# 4_USB.net
KiCad netlist of a schematic drawn in Altium Designer
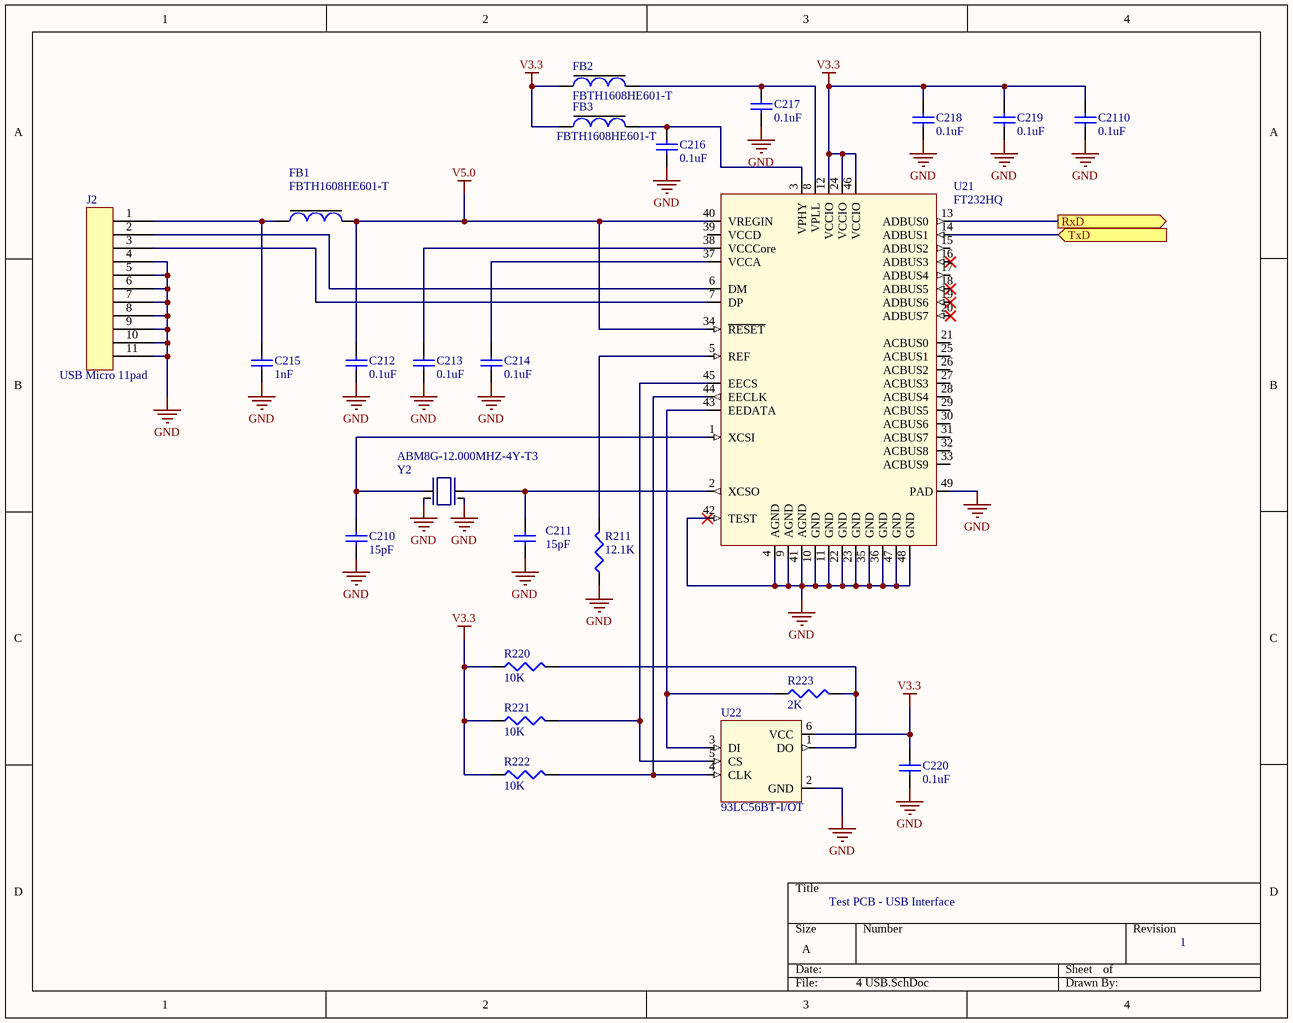
[diagram p0: 4 USB.SchDoc]

(export (version "E")
  (design (tool "Eeschema 10.0.6"))
  (components
    (comp (ref "C210")
      (value "15pF")
      (footprint "C0603")
      (description "Capacitor, SM")
      (fields (field (name "PUBLISHER") "Altium Limited"))
      (libsource (lib "Graylark") (part "Cap SM"))
    )
    (comp (ref "C211")
      (value "15pF")
      (footprint "C0603")
      (description "Capacitor, SM")
      (fields (field (name "PUBLISHER") "Altium Limited"))
      (libsource (lib "Graylark") (part "Cap SM"))
    )
    (comp (ref "C212")
      (value "0.1uF")
      (footprint "C0402")
      (description "Capacitor, SM")
      (fields (field (name "PUBLISHER") "Altium Limited"))
      (libsource (lib "Graylark") (part "Cap SM"))
    )
    (comp (ref "C213")
      (value "0.1uF")
      (footprint "C0402")
      (description "Capacitor, SM")
      (fields (field (name "PUBLISHER") "Altium Limited"))
      (libsource (lib "Graylark") (part "Cap SM"))
    )
    (comp (ref "C214")
      (value "0.1uF")
      (footprint "C0402")
      (description "Capacitor, SM")
      (fields (field (name "PUBLISHER") "Altium Limited"))
      (libsource (lib "Graylark") (part "Cap SM"))
    )
    (comp (ref "C215")
      (value "1nF")
      (footprint "C0603")
      (description "Capacitor, SM")
      (fields (field (name "PUBLISHER") "Altium Limited"))
      (libsource (lib "Graylark") (part "Cap SM"))
    )
    (comp (ref "C216")
      (value "0.1uF")
      (footprint "C0402")
      (description "Capacitor, SM")
      (fields (field (name "PUBLISHER") "Altium Limited"))
      (libsource (lib "Graylark") (part "Cap SM"))
    )
    (comp (ref "C217")
      (value "0.1uF")
      (footprint "C0402")
      (description "Capacitor, SM")
      (fields (field (name "PUBLISHER") "Altium Limited"))
      (libsource (lib "Graylark") (part "Cap SM"))
    )
    (comp (ref "C218")
      (value "0.1uF")
      (footprint "C0402")
      (description "Capacitor, SM")
      (fields (field (name "PUBLISHER") "Altium Limited"))
      (libsource (lib "Graylark") (part "Cap SM"))
    )
    (comp (ref "C219")
      (value "0.1uF")
      (footprint "C0402")
      (description "Capacitor, SM")
      (fields (field (name "PUBLISHER") "Altium Limited"))
      (libsource (lib "Graylark") (part "Cap SM"))
    )
    (comp (ref "C220")
      (value "0.1uF")
      (footprint "C0402")
      (description "Capacitor, SM")
      (fields (field (name "PUBLISHER") "Altium Limited"))
      (libsource (lib "Graylark") (part "Cap SM"))
    )
    (comp (ref "C2110")
      (value "0.1uF")
      (footprint "C0402")
      (description "Capacitor, SM")
      (fields (field (name "PUBLISHER") "Altium Limited"))
      (libsource (lib "Graylark") (part "Cap SM"))
    )
    (comp (ref "FB1")
      (value "FBTH1608HE601-T")
      (footprint "MPZ1608")
      (libsource (lib "Graylark") (part "Ferrite Bead"))
    )
    (comp (ref "FB2")
      (value "FBTH1608HE601-T")
      (footprint "MPZ1608")
      (libsource (lib "Graylark") (part "Ferrite Bead"))
    )
    (comp (ref "FB3")
      (value "FBTH1608HE601-T")
      (footprint "MPZ1608")
      (libsource (lib "Graylark") (part "Ferrite Bead"))
    )
    (comp (ref "J2")
      (value "USB Micro 11pad")
      (footprint "FCI 10118193")
      (libsource (lib "Graylark") (part "USB Micro 11pad"))
    )
    (comp (ref "R211")
      (value "12.1K")
      (footprint "R0603")
      (description "Resistor")
      (fields (field (name "PUBLISHER") "Altium Limited"))
      (libsource (lib "Graylark") (part "Res SM"))
    )
    (comp (ref "R220")
      (value "10K")
      (footprint "R0603")
      (description "Resistor")
      (fields (field (name "PUBLISHER") "Altium Limited"))
      (libsource (lib "Graylark") (part "Res SM"))
    )
    (comp (ref "R221")
      (value "10K")
      (footprint "R0603")
      (description "Resistor")
      (fields (field (name "PUBLISHER") "Altium Limited"))
      (libsource (lib "Graylark") (part "Res SM"))
    )
    (comp (ref "R222")
      (value "10K")
      (footprint "R0603")
      (description "Resistor")
      (fields (field (name "PUBLISHER") "Altium Limited"))
      (libsource (lib "Graylark") (part "Res SM"))
    )
    (comp (ref "R223")
      (value "2K")
      (footprint "R0603")
      (description "Resistor")
      (fields (field (name "PUBLISHER") "Altium Limited"))
      (libsource (lib "Graylark") (part "Res SM"))
    )
    (comp (ref "U21")
      (value "FT232HQ")
      (footprint "QFN50P800X800X100_HS-49N")
      (description "USB interface")
      (libsource (lib "Graylark_new") (part "FT232HQ"))
    )
    (comp (ref "U22")
      (value "93LC56BT-I/OT")
      (footprint "SOT23-6")
      (libsource (lib "Graylark") (part "93LC56BT-I/OT"))
    )
    (comp (ref "Y2")
      (value "ABM8G-12.000MHZ-4Y-T3")
      (footprint "7M Series XTAL")
      (libsource (lib "Graylark") (part "Crystal 4 Terminal"))
    )
  )
  (nets
    (net (code "1") (name "/RxD") (class "Default")
      (node (ref "U21") (pin "13") (pinfunction "ADBUS0_13") (pintype "output"))
    )
    (net (code "2") (name "/TxD") (class "Default")
      (node (ref "U21") (pin "14") (pinfunction "ADBUS1_14") (pintype "input"))
    )
    (net (code "3") (name "GND") (class "Default")
      (node (ref "C210") (pin "1") (pinfunction "1_1") (pintype "passive"))
      (node (ref "C211") (pin "1") (pinfunction "1_1") (pintype "passive"))
      (node (ref "C2110") (pin "1") (pinfunction "1_1") (pintype "passive"))
      (node (ref "C212") (pin "1") (pinfunction "1_1") (pintype "passive"))
      (node (ref "C213") (pin "1") (pinfunction "1_1") (pintype "passive"))
      (node (ref "C214") (pin "1") (pinfunction "1_1") (pintype "passive"))
      (node (ref "C215") (pin "1") (pinfunction "1_1") (pintype "passive"))
      (node (ref "C216") (pin "1") (pinfunction "1_1") (pintype "passive"))
      (node (ref "C217") (pin "1") (pinfunction "1_1") (pintype "passive"))
      (node (ref "C218") (pin "1") (pinfunction "1_1") (pintype "passive"))
      (node (ref "C219") (pin "1") (pinfunction "1_1") (pintype "passive"))
      (node (ref "C220") (pin "1") (pinfunction "1_1") (pintype "passive"))
      (node (ref "J2") (pin "10") (pinfunction "10_10") (pintype "power_in"))
      (node (ref "J2") (pin "11") (pinfunction "11_11") (pintype "power_in"))
      (node (ref "J2") (pin "4") (pinfunction "4_4") (pintype "passive"))
      (node (ref "J2") (pin "5") (pinfunction "5_5") (pintype "passive"))
      (node (ref "J2") (pin "6") (pinfunction "6_6") (pintype "passive"))
      (node (ref "J2") (pin "7") (pinfunction "7_7") (pintype "passive"))
      (node (ref "J2") (pin "8") (pinfunction "8_8") (pintype "passive"))
      (node (ref "J2") (pin "9") (pinfunction "9_9") (pintype "passive"))
      (node (ref "R211") (pin "1") (pinfunction "1_1") (pintype "passive"))
      (node (ref "U21") (pin "10") (pinfunction "GND_10") (pintype "power_in"))
      (node (ref "U21") (pin "11") (pinfunction "GND_11") (pintype "power_in"))
      (node (ref "U21") (pin "22") (pinfunction "GND_22") (pintype "power_in"))
      (node (ref "U21") (pin "23") (pinfunction "GND_23") (pintype "power_in"))
      (node (ref "U21") (pin "35") (pinfunction "GND_35") (pintype "power_in"))
      (node (ref "U21") (pin "36") (pinfunction "GND_36") (pintype "power_in"))
      (node (ref "U21") (pin "4") (pinfunction "AGND_4") (pintype "power_in"))
      (node (ref "U21") (pin "41") (pinfunction "AGND_41") (pintype "power_in"))
      (node (ref "U21") (pin "42") (pinfunction "TEST_42") (pintype "input"))
      (node (ref "U21") (pin "47") (pinfunction "GND_47") (pintype "power_in"))
      (node (ref "U21") (pin "48") (pinfunction "GND_48") (pintype "power_in"))
      (node (ref "U21") (pin "49") (pinfunction "PAD_49") (pintype "passive"))
      (node (ref "U21") (pin "9") (pinfunction "AGND_9") (pintype "power_in"))
      (node (ref "U22") (pin "2") (pinfunction "GND_2") (pintype "power_in"))
      (node (ref "Y2") (pin "2") (pinfunction "2_2") (pintype "passive"))
      (node (ref "Y2") (pin "4") (pinfunction "4_4") (pintype "passive"))
    )
    (net (code "4") (name "Net-(C215-Pad2)") (class "Default")
      (node (ref "C215") (pin "2") (pinfunction "2_2") (pintype "passive"))
      (node (ref "FB1") (pin "1") (pinfunction "1_1") (pintype "passive"))
      (node (ref "J2") (pin "1") (pinfunction "1_1") (pintype "passive"))
    )
    (net (code "5") (name "Net-(U21-DM)") (class "Default")
      (node (ref "J2") (pin "2") (pinfunction "2_2") (pintype "passive"))
      (node (ref "U21") (pin "6") (pinfunction "DM_6") (pintype "bidirectional"))
    )
    (net (code "6") (name "Net-(U21-DP)") (class "Default")
      (node (ref "J2") (pin "3") (pinfunction "3_3") (pintype "passive"))
      (node (ref "U21") (pin "7") (pinfunction "DP_7") (pintype "bidirectional"))
    )
    (net (code "7") (name "Net-(U21-EECLK)") (class "Default")
      (node (ref "R222") (pin "2") (pinfunction "2_2") (pintype "passive"))
      (node (ref "U21") (pin "44") (pinfunction "EECLK_44") (pintype "output"))
      (node (ref "U22") (pin "4") (pinfunction "CLK_4") (pintype "input"))
    )
    (net (code "8") (name "Net-(U21-EECS)") (class "Default")
      (node (ref "R221") (pin "2") (pinfunction "2_2") (pintype "passive"))
      (node (ref "U21") (pin "45") (pinfunction "EECS_45") (pintype "bidirectional"))
      (node (ref "U22") (pin "5") (pinfunction "CS_5") (pintype "input"))
    )
    (net (code "9") (name "Net-(U21-EEDATA)") (class "Default")
      (node (ref "R223") (pin "1") (pinfunction "1_1") (pintype "passive"))
      (node (ref "U21") (pin "43") (pinfunction "EEDATA_43") (pintype "bidirectional"))
      (node (ref "U22") (pin "3") (pinfunction "DI_3") (pintype "input"))
    )
    (net (code "10") (name "Net-(U21-REF)") (class "Default")
      (node (ref "R211") (pin "2") (pinfunction "2_2") (pintype "passive"))
      (node (ref "U21") (pin "5") (pinfunction "REF_5") (pintype "input"))
    )
    (net (code "11") (name "Net-(U21-VCCA)") (class "Default")
      (node (ref "C214") (pin "2") (pinfunction "2_2") (pintype "passive"))
      (node (ref "U21") (pin "37") (pinfunction "VCCA_37") (pintype "power_in"))
    )
    (net (code "12") (name "Net-(U21-VCCCore)") (class "Default")
      (node (ref "C213") (pin "2") (pinfunction "2_2") (pintype "passive"))
      (node (ref "U21") (pin "38") (pinfunction "VCCCore_38") (pintype "power_in"))
    )
    (net (code "13") (name "Net-(U21-VPHY)") (class "Default")
      (node (ref "C216") (pin "2") (pinfunction "2_2") (pintype "passive"))
      (node (ref "FB3") (pin "2") (pinfunction "2_2") (pintype "passive"))
      (node (ref "U21") (pin "3") (pinfunction "VPHY_3") (pintype "power_in"))
    )
    (net (code "14") (name "Net-(U21-VPLL)") (class "Default")
      (node (ref "C217") (pin "2") (pinfunction "2_2") (pintype "passive"))
      (node (ref "FB2") (pin "2") (pinfunction "2_2") (pintype "passive"))
      (node (ref "U21") (pin "8") (pinfunction "VPLL_8") (pintype "power_in"))
    )
    (net (code "15") (name "Net-(U21-XCSI)") (class "Default")
      (node (ref "C210") (pin "2") (pinfunction "2_2") (pintype "passive"))
      (node (ref "U21") (pin "1") (pinfunction "XCSI_1") (pintype "input"))
      (node (ref "Y2") (pin "1") (pinfunction "1_1") (pintype "passive"))
    )
    (net (code "16") (name "Net-(U21-XCSO)") (class "Default")
      (node (ref "C211") (pin "2") (pinfunction "2_2") (pintype "passive"))
      (node (ref "U21") (pin "2") (pinfunction "XCSO_2") (pintype "output"))
      (node (ref "Y2") (pin "3") (pinfunction "3_3") (pintype "passive"))
    )
    (net (code "17") (name "Net-(U22-DO)") (class "Default")
      (node (ref "R220") (pin "2") (pinfunction "2_2") (pintype "passive"))
      (node (ref "R223") (pin "2") (pinfunction "2_2") (pintype "passive"))
      (node (ref "U22") (pin "1") (pinfunction "DO_1") (pintype "output"))
    )
    (net (code "18") (name "V3.3") (class "Default")
      (node (ref "C2110") (pin "2") (pinfunction "2_2") (pintype "passive"))
      (node (ref "C218") (pin "2") (pinfunction "2_2") (pintype "passive"))
      (node (ref "C219") (pin "2") (pinfunction "2_2") (pintype "passive"))
      (node (ref "C220") (pin "2") (pinfunction "2_2") (pintype "passive"))
      (node (ref "FB2") (pin "1") (pinfunction "1_1") (pintype "passive"))
      (node (ref "FB3") (pin "1") (pinfunction "1_1") (pintype "passive"))
      (node (ref "R220") (pin "1") (pinfunction "1_1") (pintype "passive"))
      (node (ref "R221") (pin "1") (pinfunction "1_1") (pintype "passive"))
      (node (ref "R222") (pin "1") (pinfunction "1_1") (pintype "passive"))
      (node (ref "U21") (pin "12") (pinfunction "VCCIO_12") (pintype "power_in"))
      (node (ref "U21") (pin "24") (pinfunction "VCCIO_24") (pintype "power_in"))
      (node (ref "U21") (pin "46") (pinfunction "VCCIO_46") (pintype "power_in"))
      (node (ref "U22") (pin "6") (pinfunction "VCC_6") (pintype "power_in"))
    )
    (net (code "19") (name "V5.0") (class "Default")
      (node (ref "C212") (pin "2") (pinfunction "2_2") (pintype "passive"))
      (node (ref "FB1") (pin "2") (pinfunction "2_2") (pintype "passive"))
      (node (ref "U21") (pin "34") (pinfunction "~{RESET}_34") (pintype "input"))
      (node (ref "U21") (pin "40") (pinfunction "VREGIN_40") (pintype "power_in"))
    )
    (net (code "20") (name "unconnected-(U21-ACBUS0-Pad21)") (class "Default")
      (node (ref "U21") (pin "21") (pinfunction "ACBUS0_21") (pintype "bidirectional"))
    )
    (net (code "21") (name "unconnected-(U21-ACBUS1-Pad25)") (class "Default")
      (node (ref "U21") (pin "25") (pinfunction "ACBUS1_25") (pintype "bidirectional"))
    )
    (net (code "22") (name "unconnected-(U21-ACBUS2-Pad26)") (class "Default")
      (node (ref "U21") (pin "26") (pinfunction "ACBUS2_26") (pintype "bidirectional"))
    )
    (net (code "23") (name "unconnected-(U21-ACBUS3-Pad27)") (class "Default")
      (node (ref "U21") (pin "27") (pinfunction "ACBUS3_27") (pintype "bidirectional"))
    )
    (net (code "24") (name "unconnected-(U21-ACBUS4-Pad28)") (class "Default")
      (node (ref "U21") (pin "28") (pinfunction "ACBUS4_28") (pintype "bidirectional"))
    )
    (net (code "25") (name "unconnected-(U21-ACBUS5-Pad29)") (class "Default")
      (node (ref "U21") (pin "29") (pinfunction "ACBUS5_29") (pintype "bidirectional"))
    )
    (net (code "26") (name "unconnected-(U21-ACBUS6-Pad30)") (class "Default")
      (node (ref "U21") (pin "30") (pinfunction "ACBUS6_30") (pintype "bidirectional"))
    )
    (net (code "27") (name "unconnected-(U21-ACBUS7-Pad31)") (class "Default")
      (node (ref "U21") (pin "31") (pinfunction "ACBUS7_31") (pintype "bidirectional"))
    )
    (net (code "28") (name "unconnected-(U21-ACBUS8-Pad32)") (class "Default")
      (node (ref "U21") (pin "32") (pinfunction "ACBUS8_32") (pintype "bidirectional"))
    )
    (net (code "29") (name "unconnected-(U21-ACBUS9-Pad33)") (class "Default")
      (node (ref "U21") (pin "33") (pinfunction "ACBUS9_33") (pintype "bidirectional"))
    )
    (net (code "30") (name "unconnected-(U21-ADBUS2-Pad15)") (class "Default")
      (node (ref "U21") (pin "15") (pinfunction "ADBUS2_15") (pintype "output"))
    )
    (net (code "31") (name "unconnected-(U21-ADBUS3-Pad16)") (class "Default")
      (node (ref "U21") (pin "16") (pinfunction "ADBUS3_16") (pintype "input+no_connect"))
    )
    (net (code "32") (name "unconnected-(U21-ADBUS4-Pad17)") (class "Default")
      (node (ref "U21") (pin "17") (pinfunction "ADBUS4_17") (pintype "output"))
    )
    (net (code "33") (name "unconnected-(U21-ADBUS5-Pad18)") (class "Default")
      (node (ref "U21") (pin "18") (pinfunction "ADBUS5_18") (pintype "input+no_connect"))
    )
    (net (code "34") (name "unconnected-(U21-ADBUS6-Pad19)") (class "Default")
      (node (ref "U21") (pin "19") (pinfunction "ADBUS6_19") (pintype "input+no_connect"))
    )
    (net (code "35") (name "unconnected-(U21-ADBUS7-Pad20)") (class "Default")
      (node (ref "U21") (pin "20") (pinfunction "ADBUS7_20") (pintype "input+no_connect"))
    )
    (net (code "36") (name "unconnected-(U21-VCCD-Pad39)") (class "Default")
      (node (ref "U21") (pin "39") (pinfunction "VCCD_39") (pintype "power_in"))
    )
  )
)
